# SLBMM.net
KiCad netlist of a schematic drawn in Altium Designer
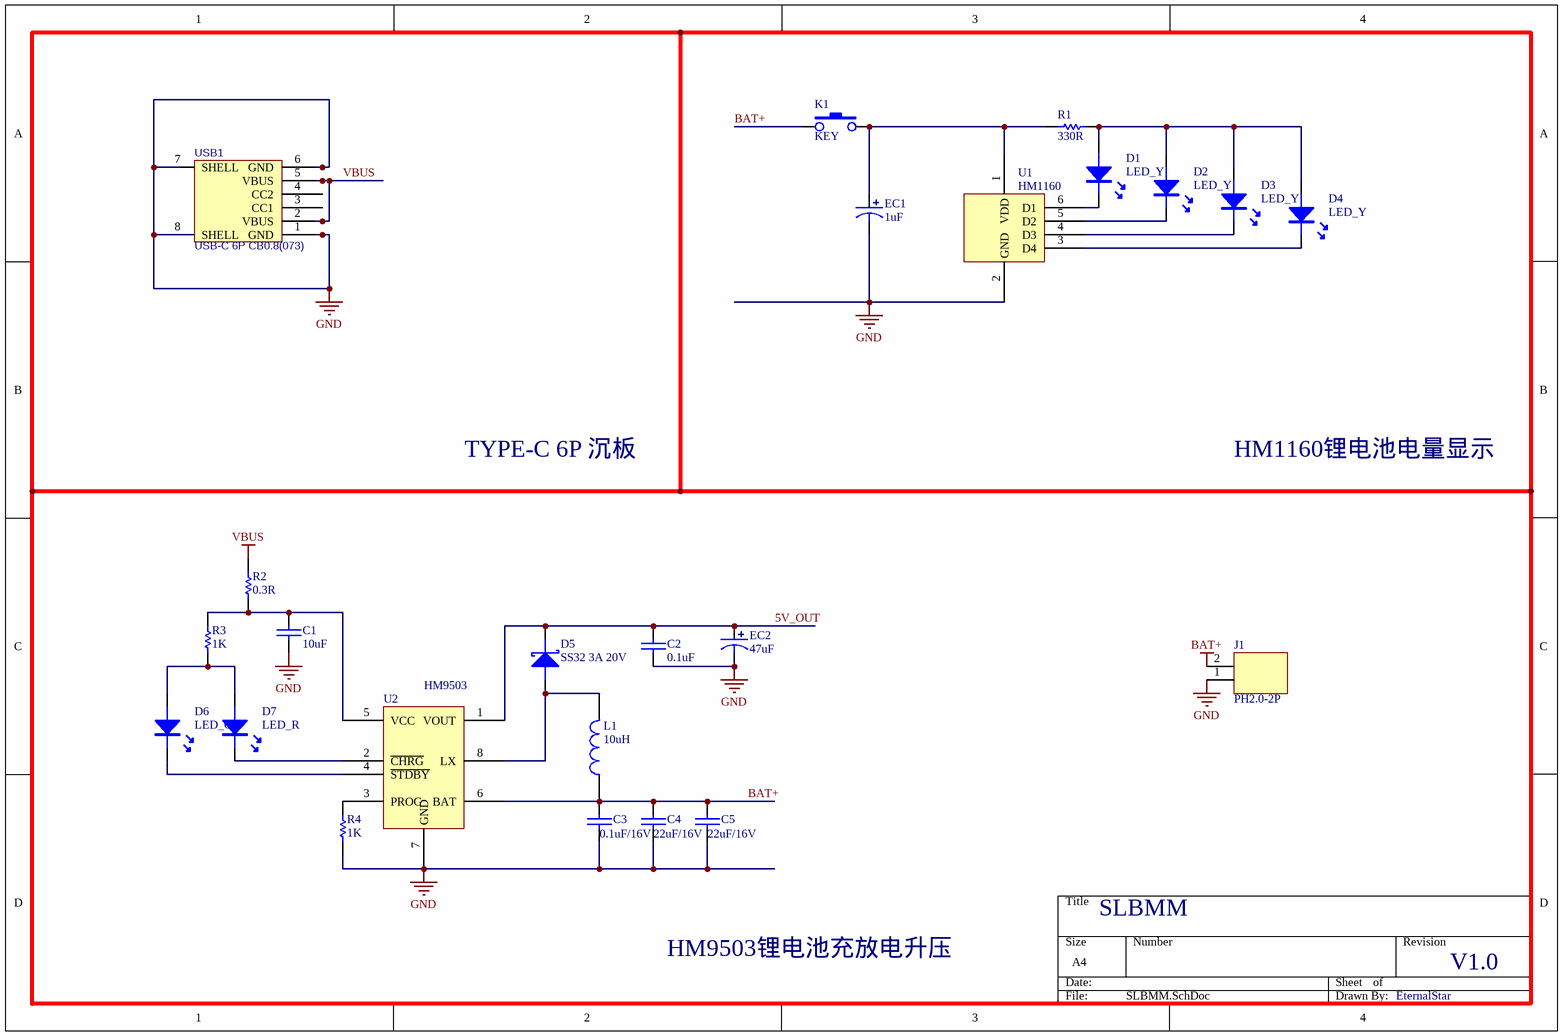
[diagram p0: SLBMM.SchDoc]

(export (version "E")
  (design (tool "Eeschema 10.0.6"))
  (components
    (comp (ref "C1")
      (value "10uF")
      (footprint "0603C")
      (description "无极性电容")
      (libsource (lib "电容") (part "CAP"))
    )
    (comp (ref "C2")
      (value "0.1uF")
      (footprint "0603C")
      (description "无极性电容")
      (libsource (lib "电容") (part "CAP"))
    )
    (comp (ref "C3")
      (value "0.1uF/16V")
      (footprint "0603C")
      (description "无极性电容")
      (libsource (lib "电容") (part "CAP"))
    )
    (comp (ref "C4")
      (value "22uF/16V")
      (footprint "0603C")
      (description "无极性电容")
      (libsource (lib "电容") (part "CAP"))
    )
    (comp (ref "C5")
      (value "22uF/16V")
      (footprint "0603C")
      (description "无极性电容")
      (libsource (lib "电容") (part "CAP"))
    )
    (comp (ref "D1") (value "LED_Y") (footprint "LED-0603Y") (libsource (lib "LED") (part "LED")))
    (comp (ref "D2") (value "LED_Y") (footprint "LED-0603Y") (libsource (lib "LED") (part "LED")))
    (comp (ref "D3") (value "LED_Y") (footprint "LED-0603Y") (libsource (lib "LED") (part "LED")))
    (comp (ref "D4") (value "LED_Y") (footprint "LED-0603Y") (libsource (lib "LED") (part "LED")))
    (comp (ref "D5")
      (value "SS32 3A 20V")
      (footprint "SMA/DO-214AC")
      (description "肖特基二极管")
      (libsource (lib "二极管") (part "DIODE SCHOTTKY"))
    )
    (comp (ref "D6") (value "LED_G") (footprint "LED-0603G") (libsource (lib "LED") (part "LED")))
    (comp (ref "D7") (value "LED_R") (footprint "LED-0603B") (libsource (lib "LED") (part "LED")))
    (comp (ref "EC1")
      (value "1uF")
      (footprint "SMD-EC4.0X4.3X5.4")
      (description "贴片电解电容")
      (libsource (lib "电容") (part "SMD_ECAP"))
    )
    (comp (ref "EC2")
      (value "47uF")
      (footprint "SMD-EC4.0X4.3X5.4")
      (description "贴片电解电容")
      (libsource (lib "电容") (part "SMD_ECAP"))
    )
    (comp (ref "J1") (value "PH2.0-2P") (footprint "PH2.0-2P") (libsource (lib "PH") (part "PH2.0-2P")))
    (comp (ref "K1") (value "KEY") (footprint "SMD-3.5x7.8x2.5_C") (libsource (lib "轻触开关") (part "KEY")))
    (comp (ref "L1")
      (value "10uH")
      (footprint "0630L")
      (description "INDUCTOR")
      (libsource (lib "电感") (part "INDUCTOR"))
    )
    (comp (ref "R1") (value "330R") (footprint "0603R") (libsource (lib "电阻") (part "RES")))
    (comp (ref "R2") (value "0.3R") (footprint "0603R") (libsource (lib "电阻") (part "RES")))
    (comp (ref "R3") (value "1K") (footprint "0603R") (libsource (lib "电阻") (part "RES")))
    (comp (ref "R4") (value "1K") (footprint "0603R") (libsource (lib "电阻") (part "RES")))
    (comp (ref "U1")
      (value "HM1160")
      (footprint "SOT23-6")
      (description "单节锂电池电量指示芯片")
      (libsource (lib "电源芯片") (part "HM1160"))
    )
    (comp (ref "U2")
      (value "HM9503")
      (footprint "ESOP8")
      (description "1A锂电池充电和5V/1A升压控制芯片")
      (libsource (lib "电源芯片") (part "HM9503"))
    )
    (comp (ref "USB1")
      (value "USB-C 6P CB0.8(073)")
      (footprint "USB-C-SMD_TYPE-C-6P-CB0.8-073")
      (fields
        (field (name "BOM_SUPPLIER PART") "C2858273")
        (field (name "BOM_MANUFACTURER PART") "TYPE-C 6P CB0.8(073)")
        (field (name "CONTRIBUTOR") "LCSC")
      )
      (libsource (lib "USB") (part "USB-C 6P CB0.8(073)"))
    )
  )
  (nets
    (net (code "1") (name "/5V_OUT") (class "Default")
      (node (ref "C2") (pin "2") (pinfunction "2_2") (pintype "passive"))
      (node (ref "D5") (pin "K") (pinfunction "K_K") (pintype "passive"))
      (node (ref "EC2") (pin "1") (pinfunction "1_1") (pintype "passive"))
      (node (ref "U2") (pin "1") (pinfunction "VOUT_1") (pintype "passive"))
    )
    (net (code "2") (name "BAT+") (class "Default")
      (node (ref "C3") (pin "2") (pinfunction "2_2") (pintype "passive"))
      (node (ref "C4") (pin "2") (pinfunction "2_2") (pintype "passive"))
      (node (ref "C5") (pin "2") (pinfunction "2_2") (pintype "passive"))
      (node (ref "J1") (pin "2") (pinfunction "2_2") (pintype "passive"))
      (node (ref "K1") (pin "1") (pinfunction "1_1") (pintype "passive"))
      (node (ref "L1") (pin "1") (pinfunction "1_1") (pintype "passive"))
      (node (ref "U2") (pin "6") (pinfunction "BAT_6") (pintype "passive"))
    )
    (net (code "3") (name "GND") (class "Default")
      (node (ref "C1") (pin "1") (pinfunction "1_1") (pintype "passive"))
      (node (ref "C2") (pin "1") (pinfunction "1_1") (pintype "passive"))
      (node (ref "C3") (pin "1") (pinfunction "1_1") (pintype "passive"))
      (node (ref "C4") (pin "1") (pinfunction "1_1") (pintype "passive"))
      (node (ref "C5") (pin "1") (pinfunction "1_1") (pintype "passive"))
      (node (ref "EC1") (pin "2") (pinfunction "2_2") (pintype "passive"))
      (node (ref "EC2") (pin "2") (pinfunction "2_2") (pintype "passive"))
      (node (ref "J1") (pin "1") (pinfunction "1_1") (pintype "passive"))
      (node (ref "R4") (pin "1") (pinfunction "1_1") (pintype "passive"))
      (node (ref "U1") (pin "2") (pinfunction "GND_2") (pintype "passive"))
      (node (ref "U2") (pin "7") (pinfunction "GND_7") (pintype "passive"))
      (node (ref "USB1") (pin "1") (pinfunction "GND_1") (pintype "passive"))
      (node (ref "USB1") (pin "6") (pinfunction "GND_6") (pintype "passive"))
      (node (ref "USB1") (pin "7") (pinfunction "SHELL_7") (pintype "passive"))
      (node (ref "USB1") (pin "8") (pinfunction "SHELL_8") (pintype "passive"))
    )
    (net (code "4") (name "Net-(D1-PadA)") (class "Default")
      (node (ref "D1") (pin "A") (pinfunction "A_A") (pintype "passive"))
      (node (ref "D2") (pin "A") (pinfunction "A_A") (pintype "passive"))
      (node (ref "D3") (pin "A") (pinfunction "A_A") (pintype "passive"))
      (node (ref "D4") (pin "A") (pinfunction "A_A") (pintype "passive"))
      (node (ref "R1") (pin "1") (pinfunction "1_1") (pintype "passive"))
    )
    (net (code "5") (name "Net-(D6-PadA)") (class "Default")
      (node (ref "D6") (pin "A") (pinfunction "A_A") (pintype "passive"))
      (node (ref "D7") (pin "A") (pinfunction "A_A") (pintype "passive"))
      (node (ref "R3") (pin "1") (pinfunction "1_1") (pintype "passive"))
    )
    (net (code "6") (name "Net-(U1-D1)") (class "Default")
      (node (ref "D1") (pin "K") (pinfunction "K_K") (pintype "passive"))
      (node (ref "U1") (pin "6") (pinfunction "D1_6") (pintype "passive"))
    )
    (net (code "7") (name "Net-(U1-D2)") (class "Default")
      (node (ref "D2") (pin "K") (pinfunction "K_K") (pintype "passive"))
      (node (ref "U1") (pin "5") (pinfunction "D2_5") (pintype "passive"))
    )
    (net (code "8") (name "Net-(U1-D3)") (class "Default")
      (node (ref "D3") (pin "K") (pinfunction "K_K") (pintype "passive"))
      (node (ref "U1") (pin "4") (pinfunction "D3_4") (pintype "passive"))
    )
    (net (code "9") (name "Net-(U1-D4)") (class "Default")
      (node (ref "D4") (pin "K") (pinfunction "K_K") (pintype "passive"))
      (node (ref "U1") (pin "3") (pinfunction "D4_3") (pintype "passive"))
    )
    (net (code "10") (name "Net-(U1-VDD)") (class "Default")
      (node (ref "EC1") (pin "1") (pinfunction "1_1") (pintype "passive"))
      (node (ref "K1") (pin "3") (pinfunction "3_3") (pintype "passive"))
      (node (ref "R1") (pin "2") (pinfunction "2_2") (pintype "passive"))
      (node (ref "U1") (pin "1") (pinfunction "VDD_1") (pintype "passive"))
    )
    (net (code "11") (name "Net-(U2-LX)") (class "Default")
      (node (ref "D5") (pin "A") (pinfunction "A_A") (pintype "passive"))
      (node (ref "L1") (pin "2") (pinfunction "2_2") (pintype "passive"))
      (node (ref "U2") (pin "8") (pinfunction "LX_8") (pintype "passive"))
    )
    (net (code "12") (name "Net-(U2-PROG)") (class "Default")
      (node (ref "R4") (pin "2") (pinfunction "2_2") (pintype "passive"))
      (node (ref "U2") (pin "3") (pinfunction "PROG_3") (pintype "passive"))
    )
    (net (code "13") (name "Net-(U2-VCC)") (class "Default")
      (node (ref "C1") (pin "2") (pinfunction "2_2") (pintype "passive"))
      (node (ref "R2") (pin "1") (pinfunction "1_1") (pintype "passive"))
      (node (ref "R3") (pin "2") (pinfunction "2_2") (pintype "passive"))
      (node (ref "U2") (pin "5") (pinfunction "VCC_5") (pintype "passive"))
    )
    (net (code "14") (name "Net-(U2-~{CHRG})") (class "Default")
      (node (ref "D7") (pin "K") (pinfunction "K_K") (pintype "passive"))
      (node (ref "U2") (pin "2") (pinfunction "~{CHRG}_2") (pintype "passive"))
    )
    (net (code "15") (name "Net-(U2-~{STDBY})") (class "Default")
      (node (ref "D6") (pin "K") (pinfunction "K_K") (pintype "passive"))
      (node (ref "U2") (pin "4") (pinfunction "~{STDBY}_4") (pintype "passive"))
    )
    (net (code "16") (name "VBUS") (class "Default")
      (node (ref "R2") (pin "2") (pinfunction "2_2") (pintype "passive"))
      (node (ref "USB1") (pin "2") (pinfunction "VBUS_2") (pintype "passive"))
      (node (ref "USB1") (pin "5") (pinfunction "VBUS_5") (pintype "passive"))
    )
    (net (code "17") (name "unconnected-(USB1-CC1-Pad3)") (class "Default")
      (node (ref "USB1") (pin "3") (pinfunction "CC1_3") (pintype "passive"))
    )
    (net (code "18") (name "unconnected-(USB1-CC2-Pad4)") (class "Default")
      (node (ref "USB1") (pin "4") (pinfunction "CC2_4") (pintype "passive"))
    )
  )
)
